# CAN.net
KiCad netlist of a schematic drawn in Altium Designer
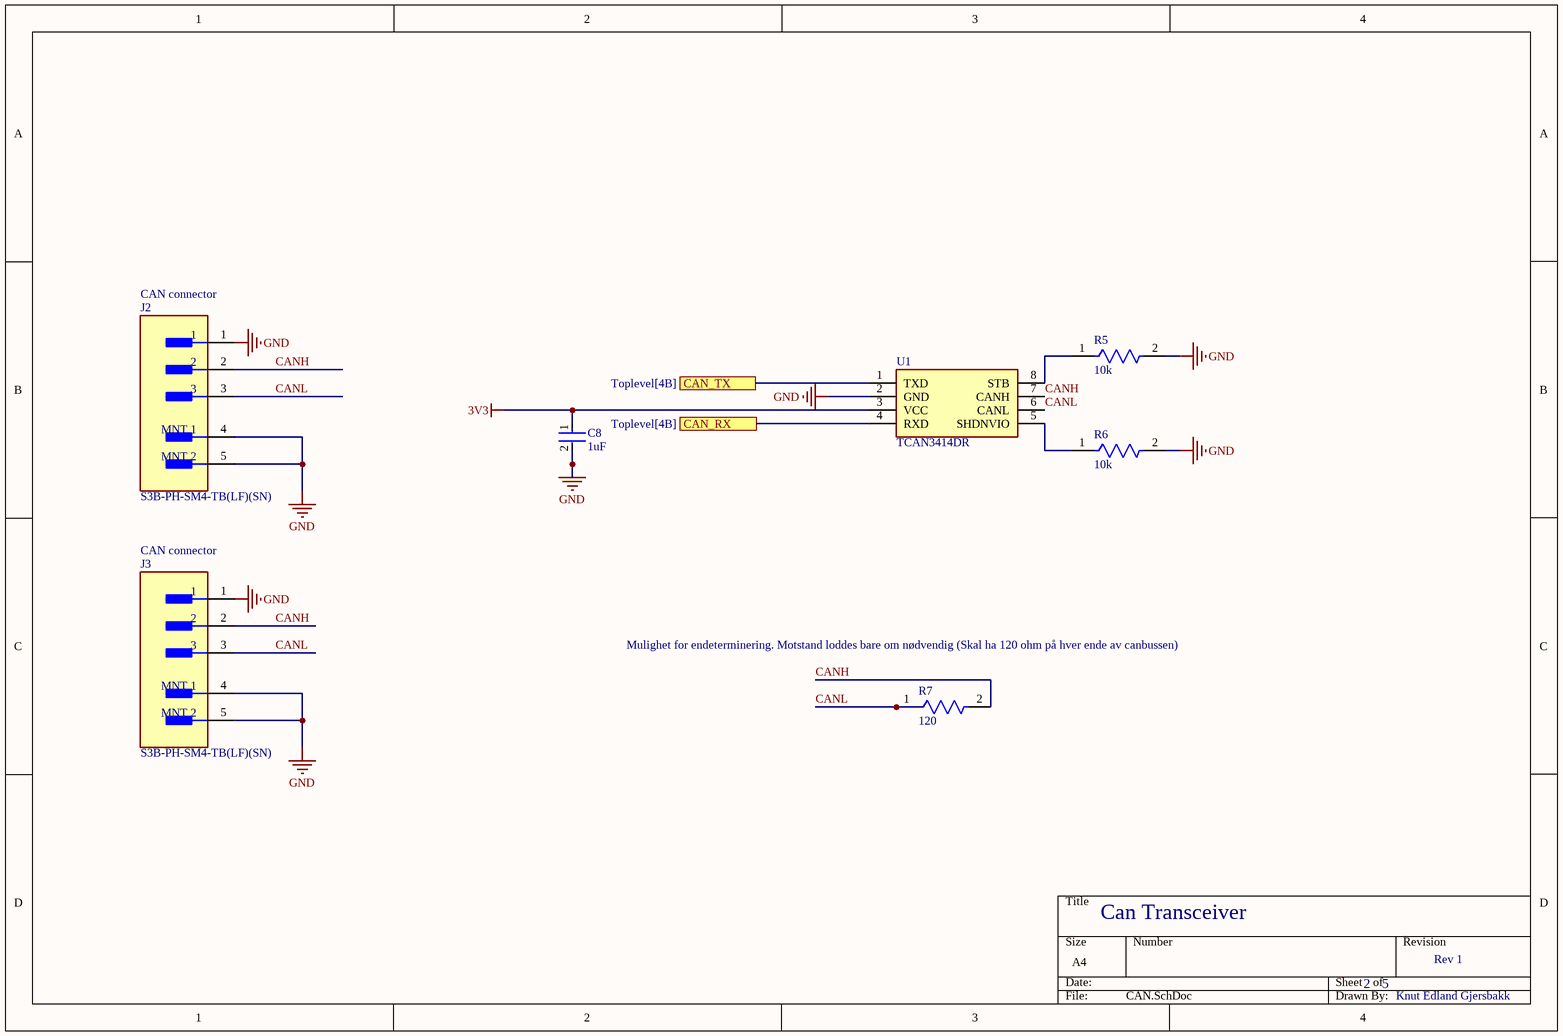
[diagram p0: CAN.SchDoc]

(export (version "E")
  (design (tool "Eeschema 10.0.6"))
  (components
    (comp (ref "C8")
      (value "1uF")
      (footprint "FP-CL10-IPC_C")
      (description "Cap Ceramic 1uF 16V X7R ±10% Pad SMD 0603 +125°C T/R\r\nCL10B105KO8NNNL")
      (fields (field (name "TOLERANCE") "10%"))
      (libsource (lib "Altium Content Vault") (part "b4654b650e69147ec39a6b967a45e02"))
    )
    (comp (ref "J2")
      (value "S3B-PH-SM4-TB(LF)(SN)")
      (footprint "FP-S3B-PH-SM4-TB_LF_SN-MFG")
      (description "Connector Header, PH Series, 3 Position, Side Entry, 2.00mm, Solder, Surface Mount, Natural.")
      (libsource (lib "UiS Aerospace") (part "38689d6f3df0f9b234c6ddcef280d85"))
    )
    (comp (ref "J3")
      (value "S3B-PH-SM4-TB(LF)(SN)")
      (footprint "FP-S3B-PH-SM4-TB_LF_SN-MFG")
      (description "Connector Header, PH Series, 3 Position, Side Entry, 2.00mm, Solder, Surface Mount, Natural.")
      (libsource (lib "UiS Aerospace") (part "38689d6f3df0f9b234c6ddcef280d85"))
    )
    (comp (ref "R5")
      (value "10k")
      (footprint "FP-RT0603-IPC_C")
      (description "RES SMD 10K OHM 1% 1/10W 0603\r\nRT0603FRE0710KL")
      (fields
        (field (name "MANUFACTURER") "Yageo")
        (field (name "OCTOPART") "https://octopart.com/rt0603fre0710kl-yageo-40009243")
      )
      (libsource (lib "Altium Content Vault") (part "1029c3af85768c4190bb7ad29bc67b5"))
    )
    (comp (ref "R6")
      (value "10k")
      (footprint "FP-RT0603-IPC_C")
      (description "RES SMD 10K OHM 1% 1/10W 0603\r\nRT0603FRE0710KL")
      (fields
        (field (name "MANUFACTURER") "Yageo")
        (field (name "OCTOPART") "https://octopart.com/rt0603fre0710kl-yageo-40009243")
      )
      (libsource (lib "Altium Content Vault") (part "1029c3af85768c4190bb7ad29bc67b5"))
    )
    (comp (ref "R7")
      (value "120")
      (footprint "FP-AF0603-IPC_C")
      (description "Anti-Sulfurated Chip Resistors Automotive Grade 120Ω 1% 100ppm/°C 0603 AF0603FR-07120RL")
      (fields (field (name "TOLERANCE") "1%"))
      (libsource (lib "Altium Content Vault") (part "1029c3af85768c4190bb7ad29bc67b5"))
    )
    (comp (ref "U1")
      (value "TCAN3414DR")
      (footprint "SamacSys:SOIC127P600X175-8N")
      (description "Integrated Circuit")
      (fields (field (name "MOUSER PART NUMBER") "595-TCAN3414DR"))
      (libsource (lib "*") (part "TCAN3414DR"))
    )
  )
  (nets
    (net (code "2") (name "/CANH") (class "Default")
      (node (ref "J2") (pin "2") (pinfunction "2_2") (pintype "passive"))
      (node (ref "J3") (pin "2") (pinfunction "2_2") (pintype "passive"))
      (node (ref "R7") (pin "2") (pinfunction "2_2") (pintype "passive"))
      (node (ref "U1") (pin "7") (pinfunction "CANH_7") (pintype "passive"))
    )
    (net (code "3") (name "/CANL") (class "Default")
      (node (ref "J2") (pin "3") (pinfunction "3_3") (pintype "passive"))
      (node (ref "J3") (pin "3") (pinfunction "3_3") (pintype "passive"))
      (node (ref "R7") (pin "1") (pinfunction "1_1") (pintype "passive"))
      (node (ref "U1") (pin "6") (pinfunction "CANL_6") (pintype "passive"))
    )
    (net (code "4") (name "/CAN_RX") (class "Default")
      (node (ref "U1") (pin "4") (pinfunction "RXD_4") (pintype "passive"))
    )
    (net (code "5") (name "/CAN_TX") (class "Default")
      (node (ref "U1") (pin "1") (pinfunction "TXD_1") (pintype "passive"))
    )
    (net (code "6") (name "3V3") (class "Default")
      (node (ref "C8") (pin "1") (pinfunction "1_1") (pintype "passive"))
      (node (ref "U1") (pin "3") (pinfunction "VCC_3") (pintype "passive"))
    )
    (net (code "7") (name "GND") (class "Default")
      (node (ref "C8") (pin "2") (pinfunction "2_2") (pintype "passive"))
      (node (ref "J2") (pin "1") (pinfunction "1_1") (pintype "passive"))
      (node (ref "J2") (pin "4") (pinfunction "MNT_1_4") (pintype "passive"))
      (node (ref "J2") (pin "5") (pinfunction "MNT_2_5") (pintype "passive"))
      (node (ref "J3") (pin "1") (pinfunction "1_1") (pintype "passive"))
      (node (ref "J3") (pin "4") (pinfunction "MNT_1_4") (pintype "passive"))
      (node (ref "J3") (pin "5") (pinfunction "MNT_2_5") (pintype "passive"))
      (node (ref "R5") (pin "2") (pinfunction "2_2") (pintype "passive"))
      (node (ref "R6") (pin "2") (pinfunction "2_2") (pintype "passive"))
      (node (ref "U1") (pin "2") (pinfunction "GND_2") (pintype "passive"))
    )
    (net (code "8") (name "Net-(U1-SHDNVIO)") (class "Default")
      (node (ref "R6") (pin "1") (pinfunction "1_1") (pintype "passive"))
      (node (ref "U1") (pin "5") (pinfunction "SHDNVIO_5") (pintype "passive"))
    )
    (net (code "9") (name "Net-(U1-STB)") (class "Default")
      (node (ref "R5") (pin "1") (pinfunction "1_1") (pintype "passive"))
      (node (ref "U1") (pin "8") (pinfunction "STB_8") (pintype "passive"))
    )
  )
)
